# Bike02.net
KiCad netlist of a schematic drawn in EAGLE
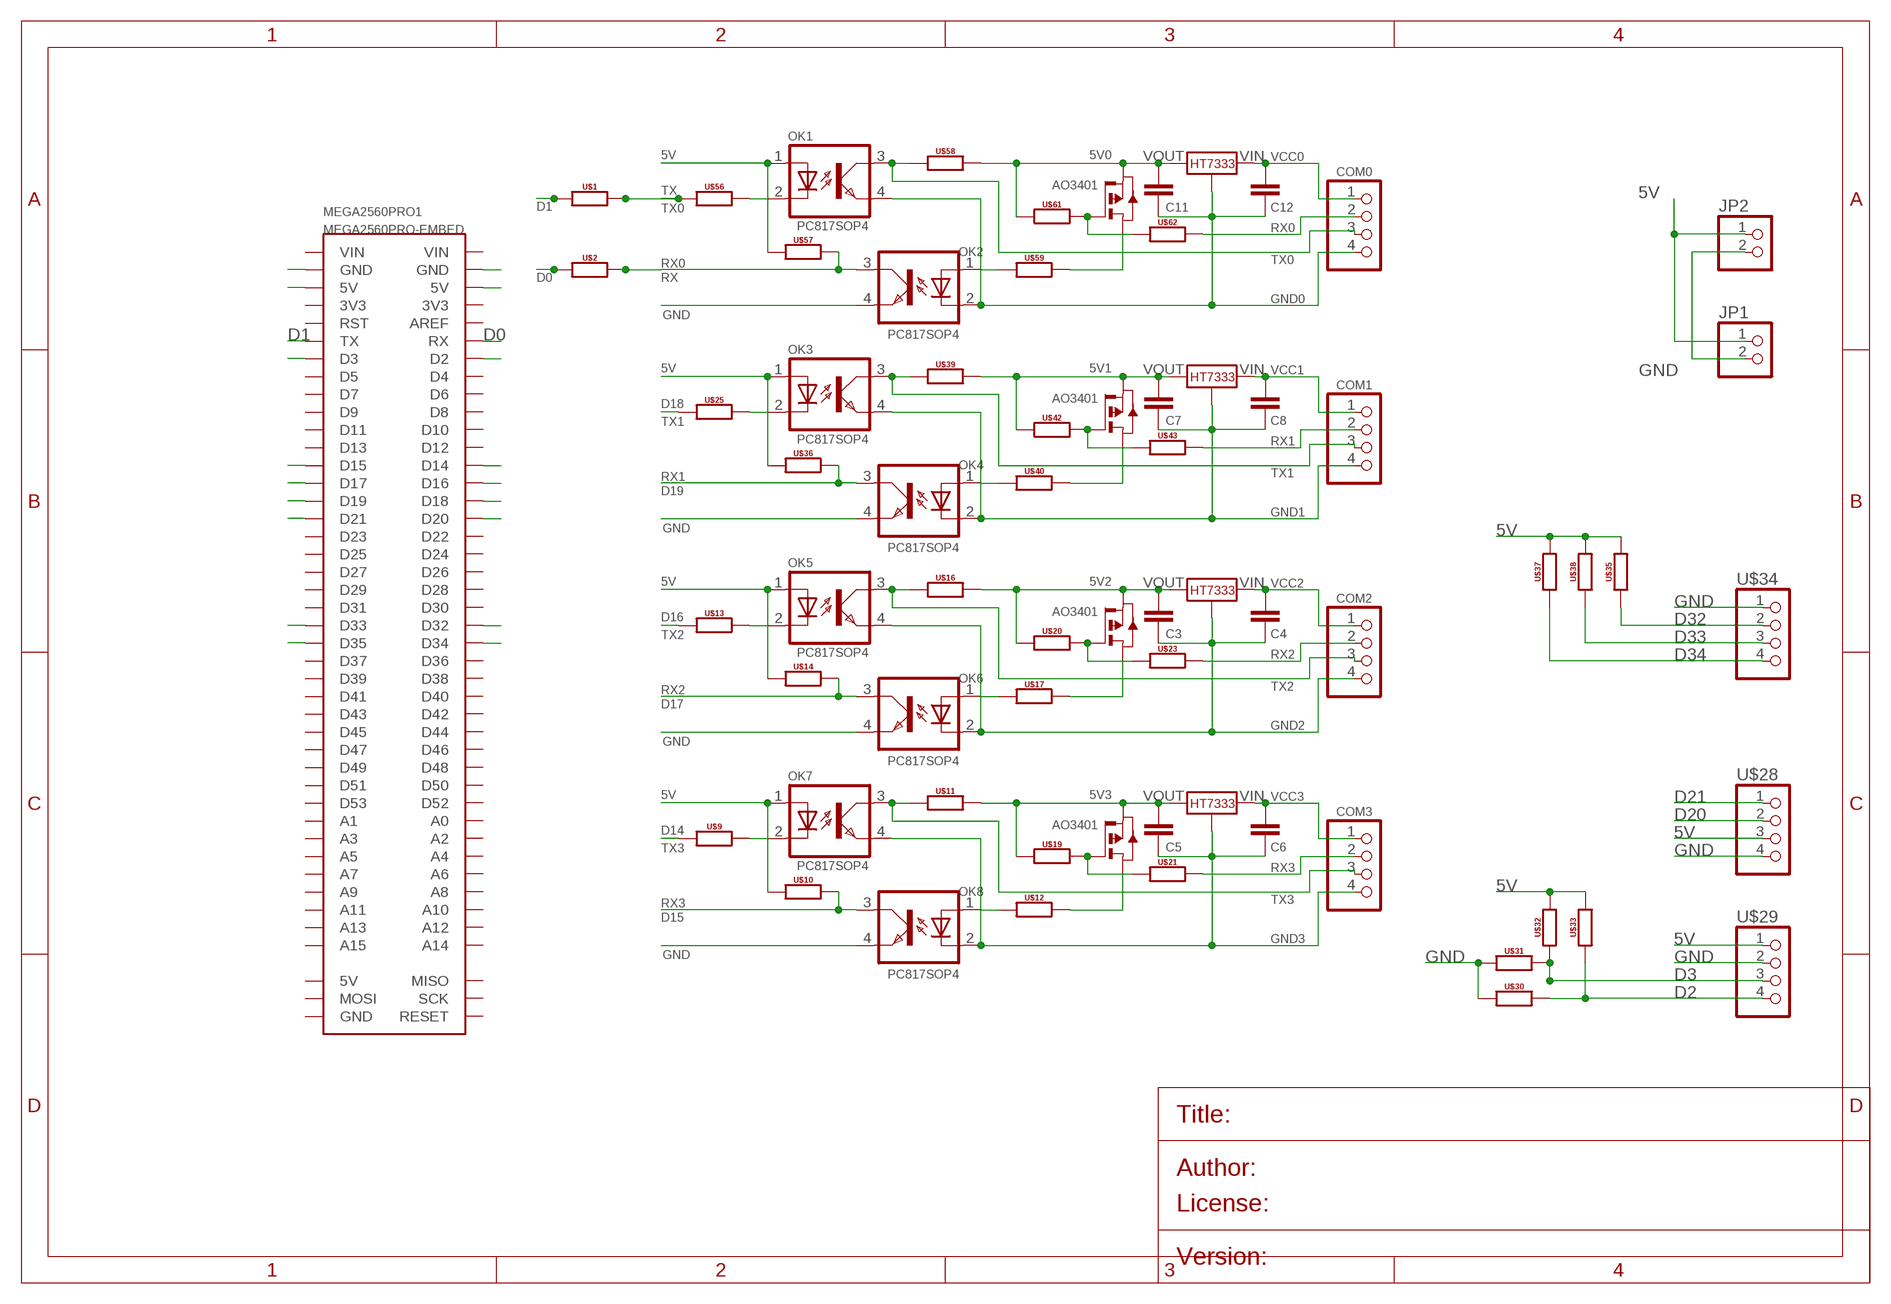
[diagram p0: schematic, sheet 1]

(export (version "E")
  (design (tool "Eeschema 10.0.6"))
  (components
    (comp (ref "C3")
      (value "CAPACITOR0805")
      (footprint "eagle-import:0805")
      (libsource (lib "eagle-import") (part "CAPACITOR0805"))
    )
    (comp (ref "C4")
      (value "CAPACITOR0805")
      (footprint "eagle-import:0805")
      (libsource (lib "eagle-import") (part "CAPACITOR0805"))
    )
    (comp (ref "C5")
      (value "CAPACITOR0805")
      (footprint "eagle-import:0805")
      (libsource (lib "eagle-import") (part "CAPACITOR0805"))
    )
    (comp (ref "C6")
      (value "CAPACITOR0805")
      (footprint "eagle-import:0805")
      (libsource (lib "eagle-import") (part "CAPACITOR0805"))
    )
    (comp (ref "C7")
      (value "CAPACITOR0805")
      (footprint "eagle-import:0805")
      (libsource (lib "eagle-import") (part "CAPACITOR0805"))
    )
    (comp (ref "C8")
      (value "CAPACITOR0805")
      (footprint "eagle-import:0805")
      (libsource (lib "eagle-import") (part "CAPACITOR0805"))
    )
    (comp (ref "C11")
      (value "CAPACITOR0805")
      (footprint "eagle-import:0805")
      (libsource (lib "eagle-import") (part "CAPACITOR0805"))
    )
    (comp (ref "C12")
      (value "CAPACITOR0805")
      (footprint "eagle-import:0805")
      (libsource (lib "eagle-import") (part "CAPACITOR0805"))
    )
    (comp (ref "COM0")
      (value "PINHD-1X4_NO_SILK")
      (footprint "eagle-import:1X04_NO_SILK")
      (libsource (lib "eagle-import") (part "PINHD-1X4_NO_SILK"))
    )
    (comp (ref "COM1")
      (value "PINHD-1X4_NO_SILK")
      (footprint "eagle-import:1X04_NO_SILK")
      (libsource (lib "eagle-import") (part "PINHD-1X4_NO_SILK"))
    )
    (comp (ref "COM2")
      (value "PINHD-1X4_NO_SILK")
      (footprint "eagle-import:1X04_NO_SILK")
      (libsource (lib "eagle-import") (part "PINHD-1X4_NO_SILK"))
    )
    (comp (ref "COM3")
      (value "PINHD-1X4_NO_SILK")
      (footprint "eagle-import:1X04_NO_SILK")
      (libsource (lib "eagle-import") (part "PINHD-1X4_NO_SILK"))
    )
    (comp (ref "JP1")
      (value "PINHD-1X2-5_NO_SILK")
      (footprint "eagle-import:1X02-5_NO_SILK")
      (libsource (lib "eagle-import") (part "PINHD-1X2-5_NO_SILK"))
    )
    (comp (ref "JP2")
      (value "PINHD-1X2-5_NO_SILK")
      (footprint "eagle-import:1X02-5_NO_SILK")
      (libsource (lib "eagle-import") (part "PINHD-1X2-5_NO_SILK"))
    )
    (comp (ref "MEGA2560PRO1")
      (value "MEGA2560PRO-EMBED")
      (footprint "eagle-import:MEGA2560PRO-EMBED")
      (libsource (lib "eagle-import") (part "MEGA2560PRO-EMBED"))
    )
    (comp (ref "OK1")
      (value "PC817SOP4")
      (footprint "eagle-import:SOP4-2.54")
      (libsource (lib "eagle-import") (part "PC817SOP4"))
    )
    (comp (ref "OK2")
      (value "PC817SOP4")
      (footprint "eagle-import:SOP4-2.54")
      (libsource (lib "eagle-import") (part "PC817SOP4"))
    )
    (comp (ref "OK3")
      (value "PC817SOP4")
      (footprint "eagle-import:SOP4-2.54")
      (libsource (lib "eagle-import") (part "PC817SOP4"))
    )
    (comp (ref "OK4")
      (value "PC817SOP4")
      (footprint "eagle-import:SOP4-2.54")
      (libsource (lib "eagle-import") (part "PC817SOP4"))
    )
    (comp (ref "OK5")
      (value "PC817SOP4")
      (footprint "eagle-import:SOP4-2.54")
      (libsource (lib "eagle-import") (part "PC817SOP4"))
    )
    (comp (ref "OK6")
      (value "PC817SOP4")
      (footprint "eagle-import:SOP4-2.54")
      (libsource (lib "eagle-import") (part "PC817SOP4"))
    )
    (comp (ref "OK7")
      (value "PC817SOP4")
      (footprint "eagle-import:SOP4-2.54")
      (libsource (lib "eagle-import") (part "PC817SOP4"))
    )
    (comp (ref "OK8")
      (value "PC817SOP4")
      (footprint "eagle-import:SOP4-2.54")
      (libsource (lib "eagle-import") (part "PC817SOP4"))
    )
    (comp (ref "U$1")
      (value "RESISTOR0805")
      (footprint "eagle-import:0805")
      (libsource (lib "eagle-import") (part "RESISTOR0805"))
    )
    (comp (ref "U$2")
      (value "RESISTOR0805")
      (footprint "eagle-import:0805")
      (libsource (lib "eagle-import") (part "RESISTOR0805"))
    )
    (comp (ref "U$9")
      (value "RESISTOR0805")
      (footprint "eagle-import:0805")
      (libsource (lib "eagle-import") (part "RESISTOR0805"))
    )
    (comp (ref "U$10")
      (value "RESISTOR0805")
      (footprint "eagle-import:0805")
      (libsource (lib "eagle-import") (part "RESISTOR0805"))
    )
    (comp (ref "U$11")
      (value "RESISTOR0805")
      (footprint "eagle-import:0805")
      (libsource (lib "eagle-import") (part "RESISTOR0805"))
    )
    (comp (ref "U$12")
      (value "RESISTOR0805")
      (footprint "eagle-import:0805")
      (libsource (lib "eagle-import") (part "RESISTOR0805"))
    )
    (comp (ref "U$13")
      (value "RESISTOR0805")
      (footprint "eagle-import:0805")
      (libsource (lib "eagle-import") (part "RESISTOR0805"))
    )
    (comp (ref "U$14")
      (value "RESISTOR0805")
      (footprint "eagle-import:0805")
      (libsource (lib "eagle-import") (part "RESISTOR0805"))
    )
    (comp (ref "U$15")
      (value "AO3401")
      (footprint "eagle-import:SOT23")
      (fields (field (name "MF") "Alpha & Omega Semiconductor"))
      (libsource (lib "eagle-import") (part "AO3401"))
    )
    (comp (ref "U$16")
      (value "RESISTOR0805")
      (footprint "eagle-import:0805")
      (libsource (lib "eagle-import") (part "RESISTOR0805"))
    )
    (comp (ref "U$17")
      (value "RESISTOR0805")
      (footprint "eagle-import:0805")
      (libsource (lib "eagle-import") (part "RESISTOR0805"))
    )
    (comp (ref "U$18")
      (value "AO3401")
      (footprint "eagle-import:SOT23")
      (fields (field (name "MF") "Alpha & Omega Semiconductor"))
      (libsource (lib "eagle-import") (part "AO3401"))
    )
    (comp (ref "U$19")
      (value "RESISTOR0805")
      (footprint "eagle-import:0805")
      (libsource (lib "eagle-import") (part "RESISTOR0805"))
    )
    (comp (ref "U$20")
      (value "RESISTOR0805")
      (footprint "eagle-import:0805")
      (libsource (lib "eagle-import") (part "RESISTOR0805"))
    )
    (comp (ref "U$21")
      (value "RESISTOR0805")
      (footprint "eagle-import:0805")
      (libsource (lib "eagle-import") (part "RESISTOR0805"))
    )
    (comp (ref "U$22")
      (value "HT7333")
      (footprint "eagle-import:SOT89")
      (libsource (lib "eagle-import") (part "HT7333"))
    )
    (comp (ref "U$23")
      (value "RESISTOR0805")
      (footprint "eagle-import:0805")
      (libsource (lib "eagle-import") (part "RESISTOR0805"))
    )
    (comp (ref "U$24")
      (value "HT7333")
      (footprint "eagle-import:SOT89")
      (libsource (lib "eagle-import") (part "HT7333"))
    )
    (comp (ref "U$25")
      (value "RESISTOR0805")
      (footprint "eagle-import:0805")
      (libsource (lib "eagle-import") (part "RESISTOR0805"))
    )
    (comp (ref "U$28")
      (value "PINHD-1X4_NO_SILK")
      (footprint "eagle-import:1X04_NO_SILK")
      (libsource (lib "eagle-import") (part "PINHD-1X4_NO_SILK"))
    )
    (comp (ref "U$29")
      (value "PINHD-1X4_NO_SILK")
      (footprint "eagle-import:1X04_NO_SILK")
      (libsource (lib "eagle-import") (part "PINHD-1X4_NO_SILK"))
    )
    (comp (ref "U$30")
      (value "RESISTOR0805")
      (footprint "eagle-import:0805")
      (libsource (lib "eagle-import") (part "RESISTOR0805"))
    )
    (comp (ref "U$31")
      (value "RESISTOR0805")
      (footprint "eagle-import:0805")
      (libsource (lib "eagle-import") (part "RESISTOR0805"))
    )
    (comp (ref "U$32")
      (value "RESISTOR0805")
      (footprint "eagle-import:0805")
      (libsource (lib "eagle-import") (part "RESISTOR0805"))
    )
    (comp (ref "U$33")
      (value "RESISTOR0805")
      (footprint "eagle-import:0805")
      (libsource (lib "eagle-import") (part "RESISTOR0805"))
    )
    (comp (ref "U$34")
      (value "PINHD-1X4_NO_SILK")
      (footprint "eagle-import:1X04_NO_SILK")
      (libsource (lib "eagle-import") (part "PINHD-1X4_NO_SILK"))
    )
    (comp (ref "U$35")
      (value "RESISTOR0805")
      (footprint "eagle-import:0805")
      (libsource (lib "eagle-import") (part "RESISTOR0805"))
    )
    (comp (ref "U$36")
      (value "RESISTOR0805")
      (footprint "eagle-import:0805")
      (libsource (lib "eagle-import") (part "RESISTOR0805"))
    )
    (comp (ref "U$37")
      (value "RESISTOR0805")
      (footprint "eagle-import:0805")
      (libsource (lib "eagle-import") (part "RESISTOR0805"))
    )
    (comp (ref "U$38")
      (value "RESISTOR0805")
      (footprint "eagle-import:0805")
      (libsource (lib "eagle-import") (part "RESISTOR0805"))
    )
    (comp (ref "U$39")
      (value "RESISTOR0805")
      (footprint "eagle-import:0805")
      (libsource (lib "eagle-import") (part "RESISTOR0805"))
    )
    (comp (ref "U$40")
      (value "RESISTOR0805")
      (footprint "eagle-import:0805")
      (libsource (lib "eagle-import") (part "RESISTOR0805"))
    )
    (comp (ref "U$41")
      (value "AO3401")
      (footprint "eagle-import:SOT23")
      (fields (field (name "MF") "Alpha & Omega Semiconductor"))
      (libsource (lib "eagle-import") (part "AO3401"))
    )
    (comp (ref "U$42")
      (value "RESISTOR0805")
      (footprint "eagle-import:0805")
      (libsource (lib "eagle-import") (part "RESISTOR0805"))
    )
    (comp (ref "U$43")
      (value "RESISTOR0805")
      (footprint "eagle-import:0805")
      (libsource (lib "eagle-import") (part "RESISTOR0805"))
    )
    (comp (ref "U$44")
      (value "HT7333")
      (footprint "eagle-import:SOT89")
      (libsource (lib "eagle-import") (part "HT7333"))
    )
    (comp (ref "U$56")
      (value "RESISTOR0805")
      (footprint "eagle-import:0805")
      (libsource (lib "eagle-import") (part "RESISTOR0805"))
    )
    (comp (ref "U$57")
      (value "RESISTOR0805")
      (footprint "eagle-import:0805")
      (libsource (lib "eagle-import") (part "RESISTOR0805"))
    )
    (comp (ref "U$58")
      (value "RESISTOR0805")
      (footprint "eagle-import:0805")
      (libsource (lib "eagle-import") (part "RESISTOR0805"))
    )
    (comp (ref "U$59")
      (value "RESISTOR0805")
      (footprint "eagle-import:0805")
      (libsource (lib "eagle-import") (part "RESISTOR0805"))
    )
    (comp (ref "U$60")
      (value "AO3401")
      (footprint "eagle-import:SOT23")
      (fields (field (name "MF") "Alpha & Omega Semiconductor"))
      (libsource (lib "eagle-import") (part "AO3401"))
    )
    (comp (ref "U$61")
      (value "RESISTOR0805")
      (footprint "eagle-import:0805")
      (libsource (lib "eagle-import") (part "RESISTOR0805"))
    )
    (comp (ref "U$62")
      (value "RESISTOR0805")
      (footprint "eagle-import:0805")
      (libsource (lib "eagle-import") (part "RESISTOR0805"))
    )
    (comp (ref "U$63")
      (value "HT7333")
      (footprint "eagle-import:SOT89")
      (libsource (lib "eagle-import") (part "HT7333"))
    )
  )
  (nets
    (net (code "1") (name "/5V") (class "Default")
      (node (ref "JP1") (pin "1") (pinfunction "1_1") (pintype "passive"))
      (node (ref "JP2") (pin "1") (pinfunction "1_1") (pintype "passive"))
      (node (ref "MEGA2560PRO1") (pin "5V@1") (pinfunction "5V_5V@1") (pintype "bidirectional"))
      (node (ref "MEGA2560PRO1") (pin "5V@2") (pinfunction "5V_5V@2") (pintype "bidirectional"))
      (node (ref "OK1") (pin "1") (pinfunction "A_1") (pintype "passive"))
      (node (ref "OK3") (pin "1") (pinfunction "A_1") (pintype "passive"))
      (node (ref "OK5") (pin "1") (pinfunction "A_1") (pintype "passive"))
      (node (ref "OK7") (pin "1") (pinfunction "A_1") (pintype "passive"))
      (node (ref "U$10") (pin "1") (pinfunction "1_1") (pintype "passive"))
      (node (ref "U$14") (pin "1") (pinfunction "1_1") (pintype "passive"))
      (node (ref "U$28") (pin "3") (pinfunction "3_3") (pintype "passive"))
      (node (ref "U$29") (pin "1") (pinfunction "1_1") (pintype "passive"))
      (node (ref "U$32") (pin "2") (pinfunction "2_2") (pintype "passive"))
      (node (ref "U$33") (pin "2") (pinfunction "2_2") (pintype "passive"))
      (node (ref "U$35") (pin "2") (pinfunction "2_2") (pintype "passive"))
      (node (ref "U$36") (pin "1") (pinfunction "1_1") (pintype "passive"))
      (node (ref "U$37") (pin "2") (pinfunction "2_2") (pintype "passive"))
      (node (ref "U$38") (pin "2") (pinfunction "2_2") (pintype "passive"))
      (node (ref "U$57") (pin "1") (pinfunction "1_1") (pintype "passive"))
    )
    (net (code "2") (name "/5V0") (class "Default")
      (node (ref "C11") (pin "1") (pinfunction "1_1") (pintype "passive"))
      (node (ref "U$58") (pin "2") (pinfunction "2_2") (pintype "passive"))
      (node (ref "U$60") (pin "2") (pinfunction "S_2") (pintype "passive"))
      (node (ref "U$61") (pin "1") (pinfunction "1_1") (pintype "passive"))
      (node (ref "U$63") (pin "VOUT") (pinfunction "VOUT_VOUT") (pintype "bidirectional"))
    )
    (net (code "3") (name "/5V1") (class "Default")
      (node (ref "C7") (pin "1") (pinfunction "1_1") (pintype "passive"))
      (node (ref "U$39") (pin "2") (pinfunction "2_2") (pintype "passive"))
      (node (ref "U$41") (pin "2") (pinfunction "S_2") (pintype "passive"))
      (node (ref "U$42") (pin "1") (pinfunction "1_1") (pintype "passive"))
      (node (ref "U$44") (pin "VOUT") (pinfunction "VOUT_VOUT") (pintype "bidirectional"))
    )
    (net (code "4") (name "/5V2") (class "Default")
      (node (ref "C3") (pin "1") (pinfunction "1_1") (pintype "passive"))
      (node (ref "U$16") (pin "2") (pinfunction "2_2") (pintype "passive"))
      (node (ref "U$18") (pin "2") (pinfunction "S_2") (pintype "passive"))
      (node (ref "U$20") (pin "1") (pinfunction "1_1") (pintype "passive"))
      (node (ref "U$24") (pin "VOUT") (pinfunction "VOUT_VOUT") (pintype "bidirectional"))
    )
    (net (code "5") (name "/5V3") (class "Default")
      (node (ref "C5") (pin "1") (pinfunction "1_1") (pintype "passive"))
      (node (ref "U$11") (pin "2") (pinfunction "2_2") (pintype "passive"))
      (node (ref "U$15") (pin "2") (pinfunction "S_2") (pintype "passive"))
      (node (ref "U$19") (pin "1") (pinfunction "1_1") (pintype "passive"))
      (node (ref "U$22") (pin "VOUT") (pinfunction "VOUT_VOUT") (pintype "bidirectional"))
    )
    (net (code "6") (name "/D0") (class "Default")
      (node (ref "MEGA2560PRO1") (pin "RX") (pinfunction "RX_RX") (pintype "bidirectional"))
      (node (ref "U$2") (pin "1") (pinfunction "1_1") (pintype "passive"))
    )
    (net (code "7") (name "/D1") (class "Default")
      (node (ref "MEGA2560PRO1") (pin "TX") (pinfunction "TX_TX") (pintype "bidirectional"))
      (node (ref "U$1") (pin "1") (pinfunction "1_1") (pintype "passive"))
    )
    (net (code "8") (name "/D2") (class "Default")
      (node (ref "MEGA2560PRO1") (pin "D2") (pinfunction "D2_D2") (pintype "bidirectional"))
      (node (ref "U$29") (pin "4") (pinfunction "4_4") (pintype "passive"))
      (node (ref "U$30") (pin "2") (pinfunction "2_2") (pintype "passive"))
      (node (ref "U$33") (pin "1") (pinfunction "1_1") (pintype "passive"))
    )
    (net (code "9") (name "/D3") (class "Default")
      (node (ref "MEGA2560PRO1") (pin "D3") (pinfunction "D3_D3") (pintype "bidirectional"))
      (node (ref "U$29") (pin "3") (pinfunction "3_3") (pintype "passive"))
      (node (ref "U$31") (pin "2") (pinfunction "2_2") (pintype "passive"))
      (node (ref "U$32") (pin "1") (pinfunction "1_1") (pintype "passive"))
    )
    (net (code "10") (name "/D14") (class "Default")
      (node (ref "MEGA2560PRO1") (pin "D14") (pinfunction "D14_D14") (pintype "bidirectional"))
      (node (ref "U$9") (pin "1") (pinfunction "1_1") (pintype "passive"))
    )
    (net (code "11") (name "/D15") (class "Default")
      (node (ref "MEGA2560PRO1") (pin "D15") (pinfunction "D15_D15") (pintype "bidirectional"))
      (node (ref "OK8") (pin "3") (pinfunction "COL_3") (pintype "passive"))
      (node (ref "U$10") (pin "2") (pinfunction "2_2") (pintype "passive"))
    )
    (net (code "12") (name "/D16") (class "Default")
      (node (ref "MEGA2560PRO1") (pin "D16") (pinfunction "D16_D16") (pintype "bidirectional"))
      (node (ref "U$13") (pin "1") (pinfunction "1_1") (pintype "passive"))
    )
    (net (code "13") (name "/D17") (class "Default")
      (node (ref "MEGA2560PRO1") (pin "D17") (pinfunction "D17_D17") (pintype "bidirectional"))
      (node (ref "OK6") (pin "3") (pinfunction "COL_3") (pintype "passive"))
      (node (ref "U$14") (pin "2") (pinfunction "2_2") (pintype "passive"))
    )
    (net (code "14") (name "/D18") (class "Default")
      (node (ref "MEGA2560PRO1") (pin "D18") (pinfunction "D18_D18") (pintype "bidirectional"))
      (node (ref "U$25") (pin "1") (pinfunction "1_1") (pintype "passive"))
    )
    (net (code "15") (name "/D19") (class "Default")
      (node (ref "MEGA2560PRO1") (pin "D19") (pinfunction "D19_D19") (pintype "bidirectional"))
      (node (ref "OK4") (pin "3") (pinfunction "COL_3") (pintype "passive"))
      (node (ref "U$36") (pin "2") (pinfunction "2_2") (pintype "passive"))
    )
    (net (code "16") (name "/D20") (class "Default")
      (node (ref "MEGA2560PRO1") (pin "D20") (pinfunction "D20_D20") (pintype "bidirectional"))
      (node (ref "U$28") (pin "2") (pinfunction "2_2") (pintype "passive"))
    )
    (net (code "17") (name "/D21") (class "Default")
      (node (ref "MEGA2560PRO1") (pin "D21") (pinfunction "D21_D21") (pintype "bidirectional"))
      (node (ref "U$28") (pin "1") (pinfunction "1_1") (pintype "passive"))
    )
    (net (code "18") (name "/D32") (class "Default")
      (node (ref "MEGA2560PRO1") (pin "D32") (pinfunction "D32_D32") (pintype "bidirectional"))
      (node (ref "U$34") (pin "2") (pinfunction "2_2") (pintype "passive"))
      (node (ref "U$35") (pin "1") (pinfunction "1_1") (pintype "passive"))
    )
    (net (code "19") (name "/D33") (class "Default")
      (node (ref "MEGA2560PRO1") (pin "D33") (pinfunction "D33_D33") (pintype "bidirectional"))
      (node (ref "U$34") (pin "3") (pinfunction "3_3") (pintype "passive"))
      (node (ref "U$38") (pin "1") (pinfunction "1_1") (pintype "passive"))
    )
    (net (code "20") (name "/D34") (class "Default")
      (node (ref "MEGA2560PRO1") (pin "D34") (pinfunction "D34_D34") (pintype "bidirectional"))
      (node (ref "U$34") (pin "4") (pinfunction "4_4") (pintype "passive"))
      (node (ref "U$37") (pin "1") (pinfunction "1_1") (pintype "passive"))
    )
    (net (code "21") (name "/GND") (class "Default")
      (node (ref "JP1") (pin "2") (pinfunction "2_2") (pintype "passive"))
      (node (ref "JP2") (pin "2") (pinfunction "2_2") (pintype "passive"))
      (node (ref "MEGA2560PRO1") (pin "GND@1") (pinfunction "GND_GND@1") (pintype "bidirectional"))
      (node (ref "MEGA2560PRO1") (pin "GND@2") (pinfunction "GND_GND@2") (pintype "bidirectional"))
      (node (ref "OK2") (pin "4") (pinfunction "EMIT_4") (pintype "passive"))
      (node (ref "OK4") (pin "4") (pinfunction "EMIT_4") (pintype "passive"))
      (node (ref "OK6") (pin "4") (pinfunction "EMIT_4") (pintype "passive"))
      (node (ref "OK8") (pin "4") (pinfunction "EMIT_4") (pintype "passive"))
      (node (ref "U$28") (pin "4") (pinfunction "4_4") (pintype "passive"))
      (node (ref "U$29") (pin "2") (pinfunction "2_2") (pintype "passive"))
      (node (ref "U$30") (pin "1") (pinfunction "1_1") (pintype "passive"))
      (node (ref "U$31") (pin "1") (pinfunction "1_1") (pintype "passive"))
      (node (ref "U$34") (pin "1") (pinfunction "1_1") (pintype "passive"))
    )
    (net (code "22") (name "/GND0") (class "Default")
      (node (ref "C11") (pin "2") (pinfunction "2_2") (pintype "passive"))
      (node (ref "C12") (pin "2") (pinfunction "2_2") (pintype "passive"))
      (node (ref "COM0") (pin "4") (pinfunction "4_4") (pintype "passive"))
      (node (ref "OK1") (pin "4") (pinfunction "EMIT_4") (pintype "passive"))
      (node (ref "OK2") (pin "2") (pinfunction "C_2") (pintype "passive"))
      (node (ref "U$63") (pin "GND") (pinfunction "GND_GND") (pintype "bidirectional"))
    )
    (net (code "23") (name "/GND1") (class "Default")
      (node (ref "C7") (pin "2") (pinfunction "2_2") (pintype "passive"))
      (node (ref "C8") (pin "2") (pinfunction "2_2") (pintype "passive"))
      (node (ref "COM1") (pin "4") (pinfunction "4_4") (pintype "passive"))
      (node (ref "OK3") (pin "4") (pinfunction "EMIT_4") (pintype "passive"))
      (node (ref "OK4") (pin "2") (pinfunction "C_2") (pintype "passive"))
      (node (ref "U$44") (pin "GND") (pinfunction "GND_GND") (pintype "bidirectional"))
    )
    (net (code "24") (name "/GND2") (class "Default")
      (node (ref "C3") (pin "2") (pinfunction "2_2") (pintype "passive"))
      (node (ref "C4") (pin "2") (pinfunction "2_2") (pintype "passive"))
      (node (ref "COM2") (pin "4") (pinfunction "4_4") (pintype "passive"))
      (node (ref "OK5") (pin "4") (pinfunction "EMIT_4") (pintype "passive"))
      (node (ref "OK6") (pin "2") (pinfunction "C_2") (pintype "passive"))
      (node (ref "U$24") (pin "GND") (pinfunction "GND_GND") (pintype "bidirectional"))
    )
    (net (code "25") (name "/GND3") (class "Default")
      (node (ref "C5") (pin "2") (pinfunction "2_2") (pintype "passive"))
      (node (ref "C6") (pin "2") (pinfunction "2_2") (pintype "passive"))
      (node (ref "COM3") (pin "4") (pinfunction "4_4") (pintype "passive"))
      (node (ref "OK7") (pin "4") (pinfunction "EMIT_4") (pintype "passive"))
      (node (ref "OK8") (pin "2") (pinfunction "C_2") (pintype "passive"))
      (node (ref "U$22") (pin "GND") (pinfunction "GND_GND") (pintype "bidirectional"))
    )
    (net (code "26") (name "/RX") (class "Default")
      (node (ref "OK2") (pin "3") (pinfunction "COL_3") (pintype "passive"))
      (node (ref "U$2") (pin "2") (pinfunction "2_2") (pintype "passive"))
      (node (ref "U$57") (pin "2") (pinfunction "2_2") (pintype "passive"))
    )
    (net (code "27") (name "/RX0") (class "Default")
      (node (ref "COM0") (pin "2") (pinfunction "2_2") (pintype "passive"))
      (node (ref "U$62") (pin "2") (pinfunction "2_2") (pintype "passive"))
    )
    (net (code "28") (name "/RX1") (class "Default")
      (node (ref "COM1") (pin "2") (pinfunction "2_2") (pintype "passive"))
      (node (ref "U$43") (pin "2") (pinfunction "2_2") (pintype "passive"))
    )
    (net (code "29") (name "/RX2") (class "Default")
      (node (ref "COM2") (pin "2") (pinfunction "2_2") (pintype "passive"))
      (node (ref "U$23") (pin "2") (pinfunction "2_2") (pintype "passive"))
    )
    (net (code "30") (name "/RX3") (class "Default")
      (node (ref "COM3") (pin "2") (pinfunction "2_2") (pintype "passive"))
      (node (ref "U$21") (pin "2") (pinfunction "2_2") (pintype "passive"))
    )
    (net (code "31") (name "/TX") (class "Default")
      (node (ref "U$1") (pin "2") (pinfunction "2_2") (pintype "passive"))
      (node (ref "U$56") (pin "1") (pinfunction "1_1") (pintype "passive"))
    )
    (net (code "32") (name "/TX0") (class "Default")
      (node (ref "COM0") (pin "3") (pinfunction "3_3") (pintype "passive"))
      (node (ref "OK1") (pin "3") (pinfunction "COL_3") (pintype "passive"))
      (node (ref "U$58") (pin "1") (pinfunction "1_1") (pintype "passive"))
    )
    (net (code "33") (name "/TX1") (class "Default")
      (node (ref "COM1") (pin "3") (pinfunction "3_3") (pintype "passive"))
      (node (ref "OK3") (pin "3") (pinfunction "COL_3") (pintype "passive"))
      (node (ref "U$39") (pin "1") (pinfunction "1_1") (pintype "passive"))
    )
    (net (code "34") (name "/TX2") (class "Default")
      (node (ref "COM2") (pin "3") (pinfunction "3_3") (pintype "passive"))
      (node (ref "OK5") (pin "3") (pinfunction "COL_3") (pintype "passive"))
      (node (ref "U$16") (pin "1") (pinfunction "1_1") (pintype "passive"))
    )
    (net (code "35") (name "/TX3") (class "Default")
      (node (ref "COM3") (pin "3") (pinfunction "3_3") (pintype "passive"))
      (node (ref "OK7") (pin "3") (pinfunction "COL_3") (pintype "passive"))
      (node (ref "U$11") (pin "1") (pinfunction "1_1") (pintype "passive"))
    )
    (net (code "36") (name "/VCC0") (class "Default")
      (node (ref "C12") (pin "1") (pinfunction "1_1") (pintype "passive"))
      (node (ref "COM0") (pin "1") (pinfunction "1_1") (pintype "passive"))
      (node (ref "U$63") (pin "VIN") (pinfunction "VIN_VIN") (pintype "bidirectional"))
    )
    (net (code "37") (name "/VCC1") (class "Default")
      (node (ref "C8") (pin "1") (pinfunction "1_1") (pintype "passive"))
      (node (ref "COM1") (pin "1") (pinfunction "1_1") (pintype "passive"))
      (node (ref "U$44") (pin "VIN") (pinfunction "VIN_VIN") (pintype "bidirectional"))
    )
    (net (code "38") (name "/VCC2") (class "Default")
      (node (ref "C4") (pin "1") (pinfunction "1_1") (pintype "passive"))
      (node (ref "COM2") (pin "1") (pinfunction "1_1") (pintype "passive"))
      (node (ref "U$24") (pin "VIN") (pinfunction "VIN_VIN") (pintype "bidirectional"))
    )
    (net (code "39") (name "/VCC3") (class "Default")
      (node (ref "C6") (pin "1") (pinfunction "1_1") (pintype "passive"))
      (node (ref "COM3") (pin "1") (pinfunction "1_1") (pintype "passive"))
      (node (ref "U$22") (pin "VIN") (pinfunction "VIN_VIN") (pintype "bidirectional"))
    )
    (net (code "40") (name "Net-(OK1-C)") (class "Default")
      (node (ref "OK1") (pin "2") (pinfunction "C_2") (pintype "passive"))
      (node (ref "U$56") (pin "2") (pinfunction "2_2") (pintype "passive"))
    )
    (net (code "41") (name "Net-(OK2-A)") (class "Default")
      (node (ref "OK2") (pin "1") (pinfunction "A_1") (pintype "passive"))
      (node (ref "U$59") (pin "1") (pinfunction "1_1") (pintype "passive"))
    )
    (net (code "42") (name "Net-(OK3-C)") (class "Default")
      (node (ref "OK3") (pin "2") (pinfunction "C_2") (pintype "passive"))
      (node (ref "U$25") (pin "2") (pinfunction "2_2") (pintype "passive"))
    )
    (net (code "43") (name "Net-(OK4-A)") (class "Default")
      (node (ref "OK4") (pin "1") (pinfunction "A_1") (pintype "passive"))
      (node (ref "U$40") (pin "1") (pinfunction "1_1") (pintype "passive"))
    )
    (net (code "44") (name "Net-(OK5-C)") (class "Default")
      (node (ref "OK5") (pin "2") (pinfunction "C_2") (pintype "passive"))
      (node (ref "U$13") (pin "2") (pinfunction "2_2") (pintype "passive"))
    )
    (net (code "45") (name "Net-(OK6-A)") (class "Default")
      (node (ref "OK6") (pin "1") (pinfunction "A_1") (pintype "passive"))
      (node (ref "U$17") (pin "1") (pinfunction "1_1") (pintype "passive"))
    )
    (net (code "46") (name "Net-(OK7-C)") (class "Default")
      (node (ref "OK7") (pin "2") (pinfunction "C_2") (pintype "passive"))
      (node (ref "U$9") (pin "2") (pinfunction "2_2") (pintype "passive"))
    )
    (net (code "47") (name "Net-(OK8-A)") (class "Default")
      (node (ref "OK8") (pin "1") (pinfunction "A_1") (pintype "passive"))
      (node (ref "U$12") (pin "1") (pinfunction "1_1") (pintype "passive"))
    )
    (net (code "48") (name "Net-(U$15-D)") (class "Default")
      (node (ref "U$12") (pin "2") (pinfunction "2_2") (pintype "passive"))
      (node (ref "U$15") (pin "3") (pinfunction "D_3") (pintype "passive"))
    )
    (net (code "49") (name "Net-(U$15-G)") (class "Default")
      (node (ref "U$15") (pin "1") (pinfunction "G_1") (pintype "passive"))
      (node (ref "U$19") (pin "2") (pinfunction "2_2") (pintype "passive"))
      (node (ref "U$21") (pin "1") (pinfunction "1_1") (pintype "passive"))
    )
    (net (code "50") (name "Net-(U$18-D)") (class "Default")
      (node (ref "U$17") (pin "2") (pinfunction "2_2") (pintype "passive"))
      (node (ref "U$18") (pin "3") (pinfunction "D_3") (pintype "passive"))
    )
    (net (code "51") (name "Net-(U$18-G)") (class "Default")
      (node (ref "U$18") (pin "1") (pinfunction "G_1") (pintype "passive"))
      (node (ref "U$20") (pin "2") (pinfunction "2_2") (pintype "passive"))
      (node (ref "U$23") (pin "1") (pinfunction "1_1") (pintype "passive"))
    )
    (net (code "52") (name "Net-(U$41-D)") (class "Default")
      (node (ref "U$40") (pin "2") (pinfunction "2_2") (pintype "passive"))
      (node (ref "U$41") (pin "3") (pinfunction "D_3") (pintype "passive"))
    )
    (net (code "53") (name "Net-(U$41-G)") (class "Default")
      (node (ref "U$41") (pin "1") (pinfunction "G_1") (pintype "passive"))
      (node (ref "U$42") (pin "2") (pinfunction "2_2") (pintype "passive"))
      (node (ref "U$43") (pin "1") (pinfunction "1_1") (pintype "passive"))
    )
    (net (code "54") (name "Net-(U$60-D)") (class "Default")
      (node (ref "U$59") (pin "2") (pinfunction "2_2") (pintype "passive"))
      (node (ref "U$60") (pin "3") (pinfunction "D_3") (pintype "passive"))
    )
    (net (code "55") (name "Net-(U$60-G)") (class "Default")
      (node (ref "U$60") (pin "1") (pinfunction "G_1") (pintype "passive"))
      (node (ref "U$61") (pin "2") (pinfunction "2_2") (pintype "passive"))
      (node (ref "U$62") (pin "1") (pinfunction "1_1") (pintype "passive"))
    )
    (net (code "56") (name "unconnected-(MEGA2560PRO1-3V3-Pad3V3@1)") (class "Default")
      (node (ref "MEGA2560PRO1") (pin "3V3@1") (pinfunction "3V3_3V3@1") (pintype "bidirectional"))
    )
    (net (code "57") (name "unconnected-(MEGA2560PRO1-3V3-Pad3V3@2)") (class "Default")
      (node (ref "MEGA2560PRO1") (pin "3V3@2") (pinfunction "3V3_3V3@2") (pintype "bidirectional"))
    )
    (net (code "58") (name "unconnected-(MEGA2560PRO1-5V-Pad5V@3)") (class "Default")
      (node (ref "MEGA2560PRO1") (pin "5V@3") (pinfunction "5V_5V@3") (pintype "bidirectional"))
    )
    (net (code "59") (name "unconnected-(MEGA2560PRO1-GND-PadGND@3)") (class "Default")
      (node (ref "MEGA2560PRO1") (pin "GND@3") (pinfunction "GND_GND@3") (pintype "bidirectional"))
    )
    (net (code "60") (name "unconnected-(MEGA2560PRO1-PadA0)") (class "Default")
      (node (ref "MEGA2560PRO1") (pin "A0") (pinfunction "A0_A0") (pintype "bidirectional"))
    )
    (net (code "61") (name "unconnected-(MEGA2560PRO1-PadA1)") (class "Default")
      (node (ref "MEGA2560PRO1") (pin "A1") (pinfunction "A1_A1") (pintype "bidirectional"))
    )
    (net (code "62") (name "unconnected-(MEGA2560PRO1-PadA2)") (class "Default")
      (node (ref "MEGA2560PRO1") (pin "A2") (pinfunction "A2_A2") (pintype "bidirectional"))
    )
    (net (code "63") (name "unconnected-(MEGA2560PRO1-PadA3)") (class "Default")
      (node (ref "MEGA2560PRO1") (pin "A3") (pinfunction "A3_A3") (pintype "bidirectional"))
    )
    (net (code "64") (name "unconnected-(MEGA2560PRO1-PadA4)") (class "Default")
      (node (ref "MEGA2560PRO1") (pin "A4") (pinfunction "A4_A4") (pintype "bidirectional"))
    )
    (net (code "65") (name "unconnected-(MEGA2560PRO1-PadA5)") (class "Default")
      (node (ref "MEGA2560PRO1") (pin "A5") (pinfunction "A5_A5") (pintype "bidirectional"))
    )
    (net (code "66") (name "unconnected-(MEGA2560PRO1-PadA6)") (class "Default")
      (node (ref "MEGA2560PRO1") (pin "A6") (pinfunction "A6_A6") (pintype "bidirectional"))
    )
    (net (code "67") (name "unconnected-(MEGA2560PRO1-PadA7)") (class "Default")
      (node (ref "MEGA2560PRO1") (pin "A7") (pinfunction "A7_A7") (pintype "bidirectional"))
    )
    (net (code "68") (name "unconnected-(MEGA2560PRO1-PadA8)") (class "Default")
      (node (ref "MEGA2560PRO1") (pin "A8") (pinfunction "A8_A8") (pintype "bidirectional"))
    )
    (net (code "69") (name "unconnected-(MEGA2560PRO1-PadA9)") (class "Default")
      (node (ref "MEGA2560PRO1") (pin "A9") (pinfunction "A9_A9") (pintype "bidirectional"))
    )
    (net (code "70") (name "unconnected-(MEGA2560PRO1-PadA10)") (class "Default")
      (node (ref "MEGA2560PRO1") (pin "A10") (pinfunction "A10_A10") (pintype "bidirectional"))
    )
    (net (code "71") (name "unconnected-(MEGA2560PRO1-PadA11)") (class "Default")
      (node (ref "MEGA2560PRO1") (pin "A11") (pinfunction "A11_A11") (pintype "bidirectional"))
    )
    (net (code "72") (name "unconnected-(MEGA2560PRO1-PadA12)") (class "Default")
      (node (ref "MEGA2560PRO1") (pin "A12") (pinfunction "A12_A12") (pintype "bidirectional"))
    )
    (net (code "73") (name "unconnected-(MEGA2560PRO1-PadA13)") (class "Default")
      (node (ref "MEGA2560PRO1") (pin "A13") (pinfunction "A13_A13") (pintype "bidirectional"))
    )
    (net (code "74") (name "unconnected-(MEGA2560PRO1-PadA14)") (class "Default")
      (node (ref "MEGA2560PRO1") (pin "A14") (pinfunction "A14_A14") (pintype "bidirectional"))
    )
    (net (code "75") (name "unconnected-(MEGA2560PRO1-PadA15)") (class "Default")
      (node (ref "MEGA2560PRO1") (pin "A15") (pinfunction "A15_A15") (pintype "bidirectional"))
    )
    (net (code "76") (name "unconnected-(MEGA2560PRO1-PadAREF)") (class "Default")
      (node (ref "MEGA2560PRO1") (pin "AREF") (pinfunction "AREF_AREF") (pintype "bidirectional"))
    )
    (net (code "77") (name "unconnected-(MEGA2560PRO1-PadD4)") (class "Default")
      (node (ref "MEGA2560PRO1") (pin "D4") (pinfunction "D4_D4") (pintype "bidirectional"))
    )
    (net (code "78") (name "unconnected-(MEGA2560PRO1-PadD5)") (class "Default")
      (node (ref "MEGA2560PRO1") (pin "D5") (pinfunction "D5_D5") (pintype "bidirectional"))
    )
    (net (code "79") (name "unconnected-(MEGA2560PRO1-PadD6)") (class "Default")
      (node (ref "MEGA2560PRO1") (pin "D6") (pinfunction "D6_D6") (pintype "bidirectional"))
    )
    (net (code "80") (name "unconnected-(MEGA2560PRO1-PadD7)") (class "Default")
      (node (ref "MEGA2560PRO1") (pin "D7") (pinfunction "D7_D7") (pintype "bidirectional"))
    )
    (net (code "81") (name "unconnected-(MEGA2560PRO1-PadD8)") (class "Default")
      (node (ref "MEGA2560PRO1") (pin "D8") (pinfunction "D8_D8") (pintype "bidirectional"))
    )
    (net (code "82") (name "unconnected-(MEGA2560PRO1-PadD9)") (class "Default")
      (node (ref "MEGA2560PRO1") (pin "D9") (pinfunction "D9_D9") (pintype "bidirectional"))
    )
    (net (code "83") (name "unconnected-(MEGA2560PRO1-PadD10)") (class "Default")
      (node (ref "MEGA2560PRO1") (pin "D10") (pinfunction "D10_D10") (pintype "bidirectional"))
    )
    (net (code "84") (name "unconnected-(MEGA2560PRO1-PadD11)") (class "Default")
      (node (ref "MEGA2560PRO1") (pin "D11") (pinfunction "D11_D11") (pintype "bidirectional"))
    )
    (net (code "85") (name "unconnected-(MEGA2560PRO1-PadD12)") (class "Default")
      (node (ref "MEGA2560PRO1") (pin "D12") (pinfunction "D12_D12") (pintype "bidirectional"))
    )
    (net (code "86") (name "unconnected-(MEGA2560PRO1-PadD13)") (class "Default")
      (node (ref "MEGA2560PRO1") (pin "D13") (pinfunction "D13_D13") (pintype "bidirectional"))
    )
    (net (code "87") (name "unconnected-(MEGA2560PRO1-PadD22)") (class "Default")
      (node (ref "MEGA2560PRO1") (pin "D22") (pinfunction "D22_D22") (pintype "bidirectional"))
    )
    (net (code "88") (name "unconnected-(MEGA2560PRO1-PadD23)") (class "Default")
      (node (ref "MEGA2560PRO1") (pin "D23") (pinfunction "D23_D23") (pintype "bidirectional"))
    )
    (net (code "89") (name "unconnected-(MEGA2560PRO1-PadD24)") (class "Default")
      (node (ref "MEGA2560PRO1") (pin "D24") (pinfunction "D24_D24") (pintype "bidirectional"))
    )
    (net (code "90") (name "unconnected-(MEGA2560PRO1-PadD25)") (class "Default")
      (node (ref "MEGA2560PRO1") (pin "D25") (pinfunction "D25_D25") (pintype "bidirectional"))
    )
    (net (code "91") (name "unconnected-(MEGA2560PRO1-PadD26)") (class "Default")
      (node (ref "MEGA2560PRO1") (pin "D26") (pinfunction "D26_D26") (pintype "bidirectional"))
    )
    (net (code "92") (name "unconnected-(MEGA2560PRO1-PadD27)") (class "Default")
      (node (ref "MEGA2560PRO1") (pin "D27") (pinfunction "D27_D27") (pintype "bidirectional"))
    )
    (net (code "93") (name "unconnected-(MEGA2560PRO1-PadD28)") (class "Default")
      (node (ref "MEGA2560PRO1") (pin "D28") (pinfunction "D28_D28") (pintype "bidirectional"))
    )
    (net (code "94") (name "unconnected-(MEGA2560PRO1-PadD29)") (class "Default")
      (node (ref "MEGA2560PRO1") (pin "D29") (pinfunction "D29_D29") (pintype "bidirectional"))
    )
    (net (code "95") (name "unconnected-(MEGA2560PRO1-PadD30)") (class "Default")
      (node (ref "MEGA2560PRO1") (pin "D30") (pinfunction "D30_D30") (pintype "bidirectional"))
    )
    (net (code "96") (name "unconnected-(MEGA2560PRO1-PadD31)") (class "Default")
      (node (ref "MEGA2560PRO1") (pin "D31") (pinfunction "D31_D31") (pintype "bidirectional"))
    )
    (net (code "97") (name "unconnected-(MEGA2560PRO1-PadD35)") (class "Default")
      (node (ref "MEGA2560PRO1") (pin "D35") (pinfunction "D35_D35") (pintype "bidirectional"))
    )
    (net (code "98") (name "unconnected-(MEGA2560PRO1-PadD36)") (class "Default")
      (node (ref "MEGA2560PRO1") (pin "D36") (pinfunction "D36_D36") (pintype "bidirectional"))
    )
    (net (code "99") (name "unconnected-(MEGA2560PRO1-PadD37)") (class "Default")
      (node (ref "MEGA2560PRO1") (pin "D37") (pinfunction "D37_D37") (pintype "bidirectional"))
    )
    (net (code "100") (name "unconnected-(MEGA2560PRO1-PadD38)") (class "Default")
      (node (ref "MEGA2560PRO1") (pin "D38") (pinfunction "D38_D38") (pintype "bidirectional"))
    )
    (net (code "101") (name "unconnected-(MEGA2560PRO1-PadD39)") (class "Default")
      (node (ref "MEGA2560PRO1") (pin "D39") (pinfunction "D39_D39") (pintype "bidirectional"))
    )
    (net (code "102") (name "unconnected-(MEGA2560PRO1-PadD40)") (class "Default")
      (node (ref "MEGA2560PRO1") (pin "D40") (pinfunction "D40_D40") (pintype "bidirectional"))
    )
    (net (code "103") (name "unconnected-(MEGA2560PRO1-PadD41)") (class "Default")
      (node (ref "MEGA2560PRO1") (pin "D41") (pinfunction "D41_D41") (pintype "bidirectional"))
    )
    (net (code "104") (name "unconnected-(MEGA2560PRO1-PadD42)") (class "Default")
      (node (ref "MEGA2560PRO1") (pin "D42") (pinfunction "D42_D42") (pintype "bidirectional"))
    )
    (net (code "105") (name "unconnected-(MEGA2560PRO1-PadD43)") (class "Default")
      (node (ref "MEGA2560PRO1") (pin "D43") (pinfunction "D43_D43") (pintype "bidirectional"))
    )
    (net (code "106") (name "unconnected-(MEGA2560PRO1-PadD44)") (class "Default")
      (node (ref "MEGA2560PRO1") (pin "D44") (pinfunction "D44_D44") (pintype "bidirectional"))
    )
    (net (code "107") (name "unconnected-(MEGA2560PRO1-PadD45)") (class "Default")
      (node (ref "MEGA2560PRO1") (pin "D45") (pinfunction "D45_D45") (pintype "bidirectional"))
    )
    (net (code "108") (name "unconnected-(MEGA2560PRO1-PadD46)") (class "Default")
      (node (ref "MEGA2560PRO1") (pin "D46") (pinfunction "D46_D46") (pintype "bidirectional"))
    )
    (net (code "109") (name "unconnected-(MEGA2560PRO1-PadD47)") (class "Default")
      (node (ref "MEGA2560PRO1") (pin "D47") (pinfunction "D47_D47") (pintype "bidirectional"))
    )
    (net (code "110") (name "unconnected-(MEGA2560PRO1-PadD48)") (class "Default")
      (node (ref "MEGA2560PRO1") (pin "D48") (pinfunction "D48_D48") (pintype "bidirectional"))
    )
    (net (code "111") (name "unconnected-(MEGA2560PRO1-PadD49)") (class "Default")
      (node (ref "MEGA2560PRO1") (pin "D49") (pinfunction "D49_D49") (pintype "bidirectional"))
    )
    (net (code "112") (name "unconnected-(MEGA2560PRO1-PadD50)") (class "Default")
      (node (ref "MEGA2560PRO1") (pin "D50") (pinfunction "D50_D50") (pintype "bidirectional"))
    )
    (net (code "113") (name "unconnected-(MEGA2560PRO1-PadD51)") (class "Default")
      (node (ref "MEGA2560PRO1") (pin "D51") (pinfunction "D51_D51") (pintype "bidirectional"))
    )
    (net (code "114") (name "unconnected-(MEGA2560PRO1-PadD52)") (class "Default")
      (node (ref "MEGA2560PRO1") (pin "D52") (pinfunction "D52_D52") (pintype "bidirectional"))
    )
    (net (code "115") (name "unconnected-(MEGA2560PRO1-PadD53)") (class "Default")
      (node (ref "MEGA2560PRO1") (pin "D53") (pinfunction "D53_D53") (pintype "bidirectional"))
    )
    (net (code "116") (name "unconnected-(MEGA2560PRO1-PadMISO)") (class "Default")
      (node (ref "MEGA2560PRO1") (pin "MISO") (pinfunction "MISO_MISO") (pintype "bidirectional"))
    )
    (net (code "117") (name "unconnected-(MEGA2560PRO1-PadMOSI)") (class "Default")
      (node (ref "MEGA2560PRO1") (pin "MOSI") (pinfunction "MOSI_MOSI") (pintype "bidirectional"))
    )
    (net (code "118") (name "unconnected-(MEGA2560PRO1-PadRESET)") (class "Default")
      (node (ref "MEGA2560PRO1") (pin "RESET") (pinfunction "RESET_RESET") (pintype "bidirectional"))
    )
    (net (code "119") (name "unconnected-(MEGA2560PRO1-PadRST)") (class "Default")
      (node (ref "MEGA2560PRO1") (pin "RST") (pinfunction "RST_RST") (pintype "bidirectional"))
    )
    (net (code "120") (name "unconnected-(MEGA2560PRO1-PadSCK)") (class "Default")
      (node (ref "MEGA2560PRO1") (pin "SCK") (pinfunction "SCK_SCK") (pintype "bidirectional"))
    )
    (net (code "121") (name "unconnected-(MEGA2560PRO1-VIN-PadVIN@1)") (class "Default")
      (node (ref "MEGA2560PRO1") (pin "VIN@1") (pinfunction "VIN_VIN@1") (pintype "bidirectional"))
    )
    (net (code "122") (name "unconnected-(MEGA2560PRO1-VIN-PadVIN@2)") (class "Default")
      (node (ref "MEGA2560PRO1") (pin "VIN@2") (pinfunction "VIN_VIN@2") (pintype "bidirectional"))
    )
  )
)
